# OZ440-SE140-CAR001_sheet2_power_supply.net
KiCad netlist of a schematic drawn in Altium Designer
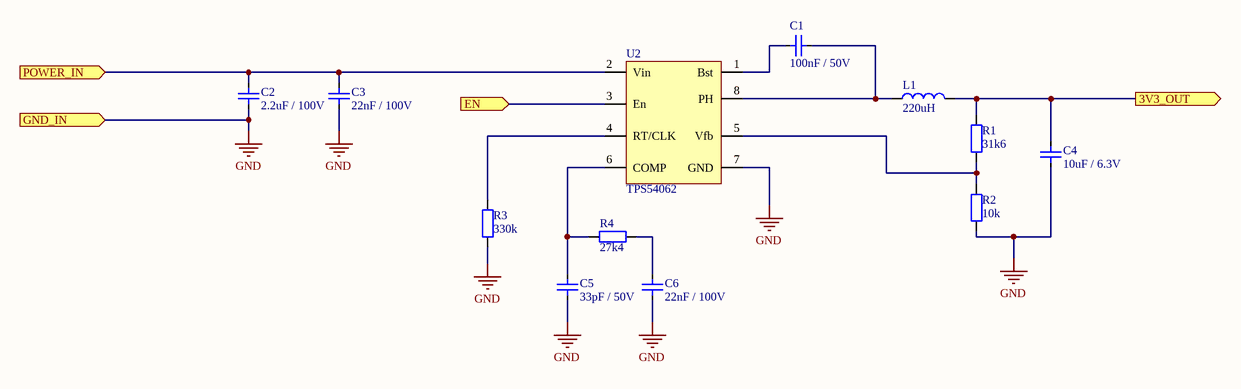
[diagram p0: OZ440-SE140-CAR001_sheet2_power_supply.SchDoc]

(export (version "E")
  (design (tool "Eeschema 10.0.6"))
  (components
    (comp (ref "C1")
      (value "CAP-SMD")
      (footprint "C0805-STD")
      (description "0805 100nF / 50V  X7R ceramic capacitor")
      (fields
        (field (name "DISPLAYED REFERENCE") "100nF / 50V")
        (field (name "TOLERANCE") "+/- 10%")
        (field (name "MANUFACTURER") "vishay")
      )
      (libsource (lib "lib_NAIO") (part "CAP-SMD"))
    )
    (comp (ref "C2")
      (value "CAP-SMD")
      (footprint "C1206-STD")
      (description "1206 2.2uF / 100V X7S ceramic capacitor")
      (fields
        (field (name "DISPLAYED REFERENCE") "2.2uF / 100V")
        (field (name "TOLERANCE") "+/- 10%")
        (field (name "MANUFACTURER") "TDK")
      )
      (libsource (lib "lib_NAIO") (part "CAP-SMD"))
    )
    (comp (ref "C3")
      (value "CAP-SMD")
      (footprint "C0805-STD")
      (description "0805 22nF / 100V X7R ceramic capacitor")
      (fields
        (field (name "DISPLAYED REFERENCE") "22nF / 100V")
        (field (name "TOLERANCE") "+/- 10%")
        (field (name "MANUFACTURER") "vishay")
      )
      (libsource (lib "lib_NAIO") (part "CAP-SMD"))
    )
    (comp (ref "C4")
      (value "CAP-SMD")
      (footprint "C0805-STD")
      (description "0805 10uF / 6.3V X5R ceramic capacitor")
      (fields
        (field (name "DISPLAYED REFERENCE") "10uF / 6.3V")
        (field (name "TOLERANCE") "+/- 10%")
        (field (name "MANUFACTURER") "Kemet")
      )
      (libsource (lib "lib_NAIO") (part "CAP-SMD"))
    )
    (comp (ref "C5")
      (value "CAP-SMD")
      (footprint "C0805-STD")
      (description "0805 33pF / 50V COG ceramic capacitor")
      (fields
        (field (name "DISPLAYED REFERENCE") "33pF / 50V")
        (field (name "TOLERANCE") "+/- 10%")
        (field (name "MANUFACTURER") "Kemet")
      )
      (libsource (lib "lib_NAIO") (part "CAP-SMD"))
    )
    (comp (ref "C6")
      (value "CAP-SMD")
      (footprint "C0805-STD")
      (description "0805 22nF / 100V X7R ceramic capacitor")
      (fields
        (field (name "DISPLAYED REFERENCE") "22nF / 100V")
        (field (name "TOLERANCE") "+/- 10%")
        (field (name "MANUFACTURER") "vishay")
      )
      (libsource (lib "lib_NAIO") (part "CAP-SMD"))
    )
    (comp (ref "L1")
      (value "IND-SMD")
      (footprint "L-SPE-4600Series_Murata")
      (description "220uH SMD inductor")
      (fields (field (name "DISPLAYED REFERENCE") "220uH") (field (name "MANUFACTURER") "MURATA"))
      (libsource (lib "lib_NAIO") (part "IND-SMD"))
    )
    (comp (ref "R1")
      (value "RES-SMD")
      (footprint "R0805-STD")
      (description "31k6 Ohm 0805 SMD resistor")
      (fields
        (field (name "DISPLAYED REFERENCE") "31k6")
        (field (name "TOLERANCE") "1%")
        (field (name "MANUFACTURER") "Vishay")
      )
      (libsource (lib "lib_NAIO") (part "RES-SMD"))
    )
    (comp (ref "R2")
      (value "RES-SMD")
      (footprint "R0805-STD")
      (description "10k Ohm 0805 SMD resistor")
      (fields
        (field (name "DISPLAYED REFERENCE") "10k")
        (field (name "TOLERANCE") "1 %")
        (field (name "MANUFACTURER") "Vishay")
      )
      (libsource (lib "lib_NAIO") (part "RES-SMD"))
    )
    (comp (ref "R3")
      (value "RES-SMD")
      (footprint "R0805-STD")
      (description "330k Ohm 0805 SMD resistor")
      (fields
        (field (name "DISPLAYED REFERENCE") "330k")
        (field (name "TOLERANCE") "1%")
        (field (name "MANUFACTURER") "Vishay")
      )
      (libsource (lib "lib_NAIO") (part "RES-SMD"))
    )
    (comp (ref "R4")
      (value "RES-SMD")
      (footprint "R0805-STD")
      (description "27k4 Ohm 0805 SMD resistor")
      (fields
        (field (name "DISPLAYED REFERENCE") "27k4")
        (field (name "TOLERANCE") "1%")
        (field (name "MANUFACTURER") "Vishay")
      )
      (libsource (lib "") (part "RES-SMD_1"))
    )
    (comp (ref "U2")
      (value "TPS54062-MSOP8")
      (footprint "MSOP08-SPE-TPS54062")
      (description "4.7V to 60V Input, 50mA Synchronous Step-Down Converter")
      (fields (field (name "DISPLAYED REFERENCE") "TPS54062") (field (name "MANUFACTURER") "TI"))
      (libsource (lib "lib_NAIO") (part "TPS54062-MSOP8"))
    )
  )
  (nets
    (net (code "1") (name "/3V3_OUT") (class "Default")
      (node (ref "C4") (pin "2") (pinfunction "2_2") (pintype "passive"))
      (node (ref "L1") (pin "2") (pinfunction "2_2") (pintype "passive"))
      (node (ref "R1") (pin "2") (pinfunction "2_2") (pintype "passive"))
    )
    (net (code "2") (name "/EN") (class "Default")
      (node (ref "U2") (pin "3") (pinfunction "En_3") (pintype "passive"))
    )
    (net (code "3") (name "/POWER_IN") (class "Default")
      (node (ref "C2") (pin "2") (pinfunction "2_2") (pintype "passive"))
      (node (ref "C3") (pin "2") (pinfunction "2_2") (pintype "passive"))
      (node (ref "U2") (pin "2") (pinfunction "Vin_2") (pintype "passive"))
    )
    (net (code "4") (name "GND") (class "Default")
      (node (ref "C2") (pin "1") (pinfunction "1_1") (pintype "passive"))
      (node (ref "C3") (pin "1") (pinfunction "1_1") (pintype "passive"))
      (node (ref "C4") (pin "1") (pinfunction "1_1") (pintype "passive"))
      (node (ref "C5") (pin "1") (pinfunction "1_1") (pintype "passive"))
      (node (ref "C6") (pin "1") (pinfunction "1_1") (pintype "passive"))
      (node (ref "R2") (pin "1") (pinfunction "1_1") (pintype "passive"))
      (node (ref "R3") (pin "1") (pinfunction "1_1") (pintype "passive"))
      (node (ref "U2") (pin "7") (pinfunction "GND_7") (pintype "passive"))
    )
    (net (code "5") (name "Net-(C6-Pad2)") (class "Default")
      (node (ref "C6") (pin "2") (pinfunction "2_2") (pintype "passive"))
      (node (ref "R4") (pin "2") (pinfunction "2_2") (pintype "passive"))
    )
    (net (code "6") (name "Net-(U2-Bst)") (class "Default")
      (node (ref "C1") (pin "1") (pinfunction "1_1") (pintype "passive"))
      (node (ref "U2") (pin "1") (pinfunction "Bst_1") (pintype "passive"))
    )
    (net (code "7") (name "Net-(U2-COMP)") (class "Default")
      (node (ref "C5") (pin "2") (pinfunction "2_2") (pintype "passive"))
      (node (ref "R4") (pin "1") (pinfunction "1_1") (pintype "passive"))
      (node (ref "U2") (pin "6") (pinfunction "COMP_6") (pintype "passive"))
    )
    (net (code "8") (name "Net-(U2-PH)") (class "Default")
      (node (ref "C1") (pin "2") (pinfunction "2_2") (pintype "passive"))
      (node (ref "L1") (pin "1") (pinfunction "1_1") (pintype "passive"))
      (node (ref "U2") (pin "8") (pinfunction "PH_8") (pintype "passive"))
    )
    (net (code "9") (name "Net-(U2-RT{slash}CLK)") (class "Default")
      (node (ref "R3") (pin "2") (pinfunction "2_2") (pintype "passive"))
      (node (ref "U2") (pin "4") (pinfunction "RT/CLK_4") (pintype "passive"))
    )
    (net (code "10") (name "Net-(U2-Vfb)") (class "Default")
      (node (ref "R1") (pin "1") (pinfunction "1_1") (pintype "passive"))
      (node (ref "R2") (pin "2") (pinfunction "2_2") (pintype "passive"))
      (node (ref "U2") (pin "5") (pinfunction "Vfb_5") (pintype "passive"))
    )
  )
)
